# tras.net
KiCad netlist of a schematic drawn in EAGLE
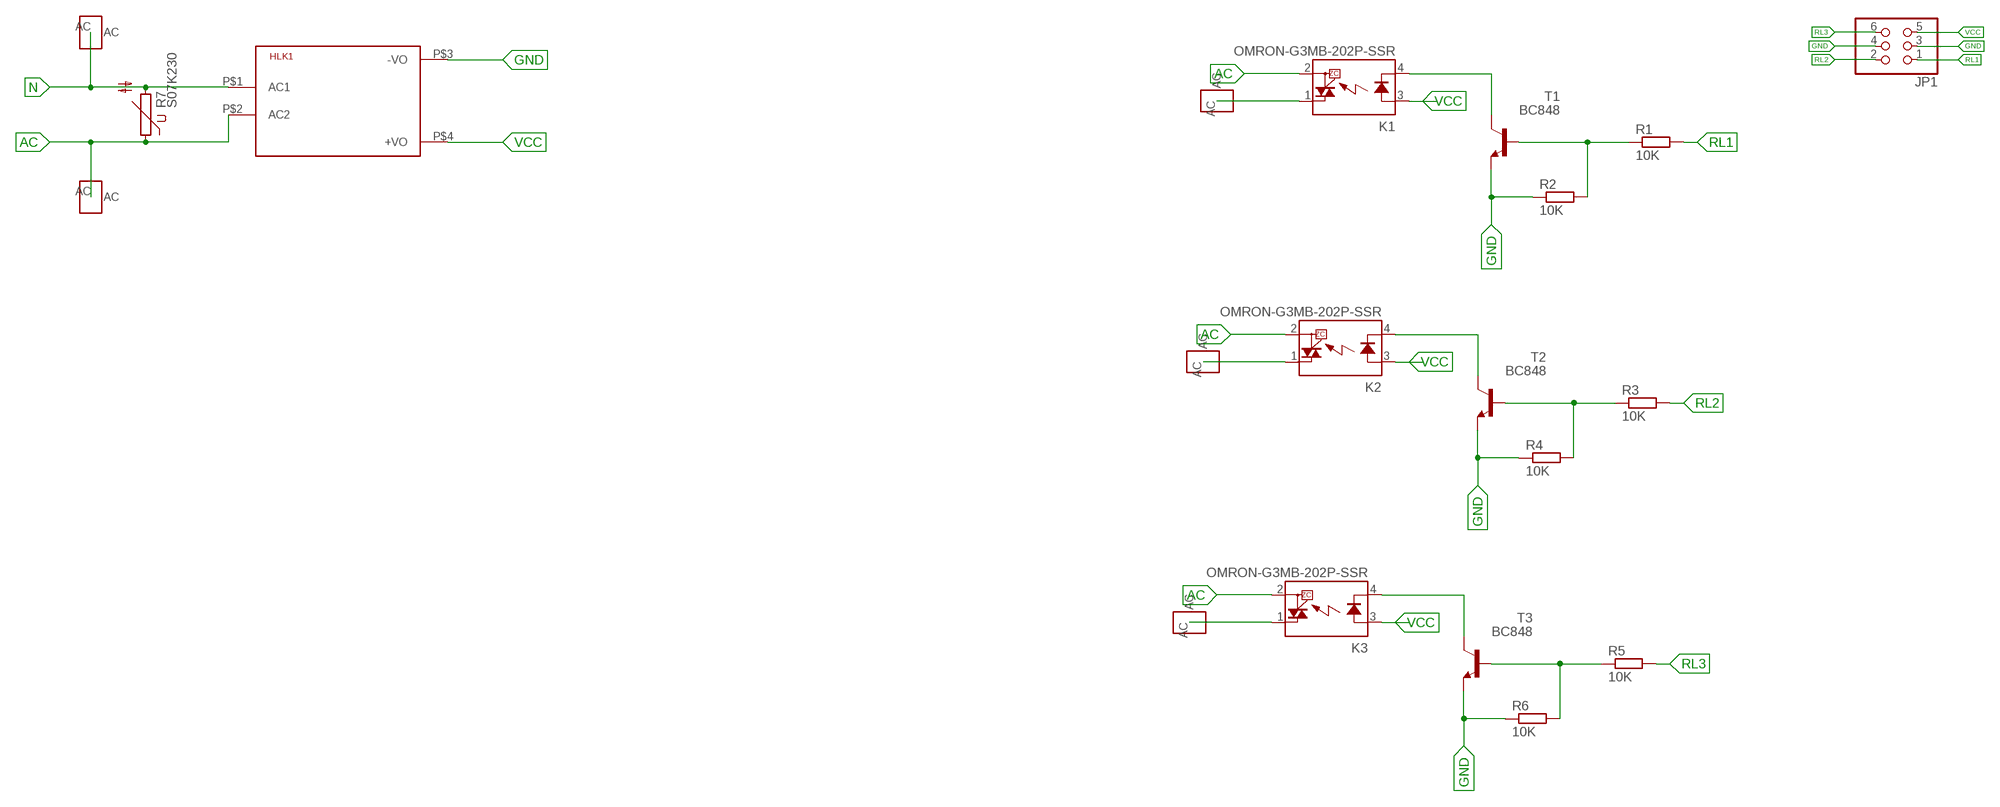
[diagram p0: schematic, sheet 1]

(export (version "E")
  (design (tool "Eeschema 10.0.6"))
  (components
    (comp (ref "AC")
      (value "PAN_AC")
      (footprint "eagle-import:PAD_AC")
      (libsource (lib "eagle-import") (part "PAN_AC"))
    )
    (comp (ref "HLK1")
      (value "HLK-PM013W")
      (footprint "eagle-import:HLK-PM01")
      (libsource (lib "eagle-import") (part "HLK-PM013W"))
    )
    (comp (ref "JP1")
      (value "PINHD-2X3M")
      (footprint "eagle-import:2X03M")
      (libsource (lib "eagle-import") (part "PINHD-2X3M"))
    )
    (comp (ref "K1")
      (value "OMRON-G3MB-202P-SSR")
      (footprint "eagle-import:OMRON-G3MB-202P-SSR")
      (libsource (lib "eagle-import") (part "OMRON-G3MB-202P-SSR"))
    )
    (comp (ref "K2")
      (value "OMRON-G3MB-202P-SSR")
      (footprint "eagle-import:OMRON-G3MB-202P-SSR")
      (libsource (lib "eagle-import") (part "OMRON-G3MB-202P-SSR"))
    )
    (comp (ref "K3")
      (value "OMRON-G3MB-202P-SSR")
      (footprint "eagle-import:OMRON-G3MB-202P-SSR")
      (libsource (lib "eagle-import") (part "OMRON-G3MB-202P-SSR"))
    )
    (comp (ref "L1")
      (value "PAN_AC")
      (footprint "eagle-import:PAD_AC")
      (libsource (lib "eagle-import") (part "PAN_AC"))
    )
    (comp (ref "L2")
      (value "PAN_AC")
      (footprint "eagle-import:PAD_AC")
      (libsource (lib "eagle-import") (part "PAN_AC"))
    )
    (comp (ref "L3")
      (value "PAN_AC")
      (footprint "eagle-import:PAD_AC")
      (libsource (lib "eagle-import") (part "PAN_AC"))
    )
    (comp (ref "N")
      (value "PAN_AC")
      (footprint "eagle-import:PAD_AC")
      (libsource (lib "eagle-import") (part "PAN_AC"))
    )
    (comp (ref "R1")
      (value "10K")
      (footprint "eagle-import:R0805")
      (libsource (lib "eagle-import") (part "R-EU_R0805"))
    )
    (comp (ref "R2")
      (value "10K")
      (footprint "eagle-import:R0805")
      (libsource (lib "eagle-import") (part "R-EU_R0805"))
    )
    (comp (ref "R3")
      (value "10K")
      (footprint "eagle-import:R0805")
      (libsource (lib "eagle-import") (part "R-EU_R0805"))
    )
    (comp (ref "R4")
      (value "10K")
      (footprint "eagle-import:R0805")
      (libsource (lib "eagle-import") (part "R-EU_R0805"))
    )
    (comp (ref "R5")
      (value "10K")
      (footprint "eagle-import:R0805")
      (libsource (lib "eagle-import") (part "R-EU_R0805"))
    )
    (comp (ref "R6")
      (value "10K")
      (footprint "eagle-import:R0805")
      (libsource (lib "eagle-import") (part "R-EU_R0805"))
    )
    (comp (ref "R7")
      (value "S07K230")
      (footprint "eagle-import:S07K230")
      (libsource (lib "eagle-import") (part "S07K230"))
    )
    (comp (ref "T1")
      (value "BC848")
      (footprint "eagle-import:SOT23")
      (libsource (lib "eagle-import") (part "BC848"))
    )
    (comp (ref "T2")
      (value "BC848")
      (footprint "eagle-import:SOT23")
      (libsource (lib "eagle-import") (part "BC848"))
    )
    (comp (ref "T3")
      (value "BC848")
      (footprint "eagle-import:SOT23")
      (libsource (lib "eagle-import") (part "BC848"))
    )
  )
  (nets
    (net (code "1") (name "AC") (class "Default")
      (node (ref "AC") (pin "AC") (pinfunction "AC_AC") (pintype "bidirectional"))
      (node (ref "HLK1") (pin "P$2") (pinfunction "AC2_P$2") (pintype "bidirectional"))
      (node (ref "K1") (pin "2") (pinfunction "DS2_2") (pintype "passive"))
      (node (ref "K2") (pin "2") (pinfunction "DS2_2") (pintype "passive"))
      (node (ref "K3") (pin "2") (pinfunction "DS2_2") (pintype "passive"))
      (node (ref "R7") (pin "1") (pinfunction "1_1") (pintype "passive"))
    )
    (net (code "2") (name "GND") (class "Default")
      (node (ref "HLK1") (pin "P$3") (pinfunction "-VO_P$3") (pintype "bidirectional"))
      (node (ref "JP1") (pin "3") (pinfunction "3_3") (pintype "passive"))
      (node (ref "JP1") (pin "4") (pinfunction "4_4") (pintype "passive"))
      (node (ref "R2") (pin "1") (pinfunction "1_1") (pintype "passive"))
      (node (ref "R4") (pin "1") (pinfunction "1_1") (pintype "passive"))
      (node (ref "R6") (pin "1") (pinfunction "1_1") (pintype "passive"))
      (node (ref "T1") (pin "2") (pinfunction "E_2") (pintype "passive"))
      (node (ref "T2") (pin "2") (pinfunction "E_2") (pintype "passive"))
      (node (ref "T3") (pin "2") (pinfunction "E_2") (pintype "passive"))
    )
    (net (code "3") (name "N") (class "Default")
      (node (ref "HLK1") (pin "P$1") (pinfunction "AC1_P$1") (pintype "bidirectional"))
      (node (ref "N") (pin "AC") (pinfunction "AC_AC") (pintype "bidirectional"))
      (node (ref "R7") (pin "2") (pinfunction "2_2") (pintype "passive"))
    )
    (net (code "4") (name "Net-(K1-DS1)") (class "Default")
      (node (ref "K1") (pin "1") (pinfunction "DS1_1") (pintype "passive"))
      (node (ref "L1") (pin "AC") (pinfunction "AC_AC") (pintype "bidirectional"))
    )
    (net (code "5") (name "Net-(K1-K)") (class "Default")
      (node (ref "K1") (pin "4") (pinfunction "K_4") (pintype "passive"))
      (node (ref "T1") (pin "3") (pinfunction "C_3") (pintype "passive"))
    )
    (net (code "6") (name "Net-(K2-DS1)") (class "Default")
      (node (ref "K2") (pin "1") (pinfunction "DS1_1") (pintype "passive"))
      (node (ref "L2") (pin "AC") (pinfunction "AC_AC") (pintype "bidirectional"))
    )
    (net (code "7") (name "Net-(K2-K)") (class "Default")
      (node (ref "K2") (pin "4") (pinfunction "K_4") (pintype "passive"))
      (node (ref "T2") (pin "3") (pinfunction "C_3") (pintype "passive"))
    )
    (net (code "8") (name "Net-(K3-DS1)") (class "Default")
      (node (ref "K3") (pin "1") (pinfunction "DS1_1") (pintype "passive"))
      (node (ref "L3") (pin "AC") (pinfunction "AC_AC") (pintype "bidirectional"))
    )
    (net (code "9") (name "Net-(K3-K)") (class "Default")
      (node (ref "K3") (pin "4") (pinfunction "K_4") (pintype "passive"))
      (node (ref "T3") (pin "3") (pinfunction "C_3") (pintype "passive"))
    )
    (net (code "10") (name "Net-(T1-B)") (class "Default")
      (node (ref "R1") (pin "1") (pinfunction "1_1") (pintype "passive"))
      (node (ref "R2") (pin "2") (pinfunction "2_2") (pintype "passive"))
      (node (ref "T1") (pin "1") (pinfunction "B_1") (pintype "passive"))
    )
    (net (code "11") (name "Net-(T2-B)") (class "Default")
      (node (ref "R3") (pin "1") (pinfunction "1_1") (pintype "passive"))
      (node (ref "R4") (pin "2") (pinfunction "2_2") (pintype "passive"))
      (node (ref "T2") (pin "1") (pinfunction "B_1") (pintype "passive"))
    )
    (net (code "12") (name "Net-(T3-B)") (class "Default")
      (node (ref "R5") (pin "1") (pinfunction "1_1") (pintype "passive"))
      (node (ref "R6") (pin "2") (pinfunction "2_2") (pintype "passive"))
      (node (ref "T3") (pin "1") (pinfunction "B_1") (pintype "passive"))
    )
    (net (code "13") (name "RL1") (class "Default")
      (node (ref "JP1") (pin "1") (pinfunction "1_1") (pintype "passive"))
      (node (ref "R1") (pin "2") (pinfunction "2_2") (pintype "passive"))
    )
    (net (code "14") (name "RL2") (class "Default")
      (node (ref "JP1") (pin "2") (pinfunction "2_2") (pintype "passive"))
      (node (ref "R3") (pin "2") (pinfunction "2_2") (pintype "passive"))
    )
    (net (code "15") (name "RL3") (class "Default")
      (node (ref "JP1") (pin "6") (pinfunction "6_6") (pintype "passive"))
      (node (ref "R5") (pin "2") (pinfunction "2_2") (pintype "passive"))
    )
    (net (code "16") (name "VCC") (class "Default")
      (node (ref "HLK1") (pin "P$4") (pinfunction "+VO_P$4") (pintype "bidirectional"))
      (node (ref "JP1") (pin "5") (pinfunction "5_5") (pintype "passive"))
      (node (ref "K1") (pin "3") (pinfunction "A_3") (pintype "passive"))
      (node (ref "K2") (pin "3") (pinfunction "A_3") (pintype "passive"))
      (node (ref "K3") (pin "3") (pinfunction "A_3") (pintype "passive"))
    )
  )
)
